# Conector.net
KiCad netlist of a schematic drawn in Altium Designer
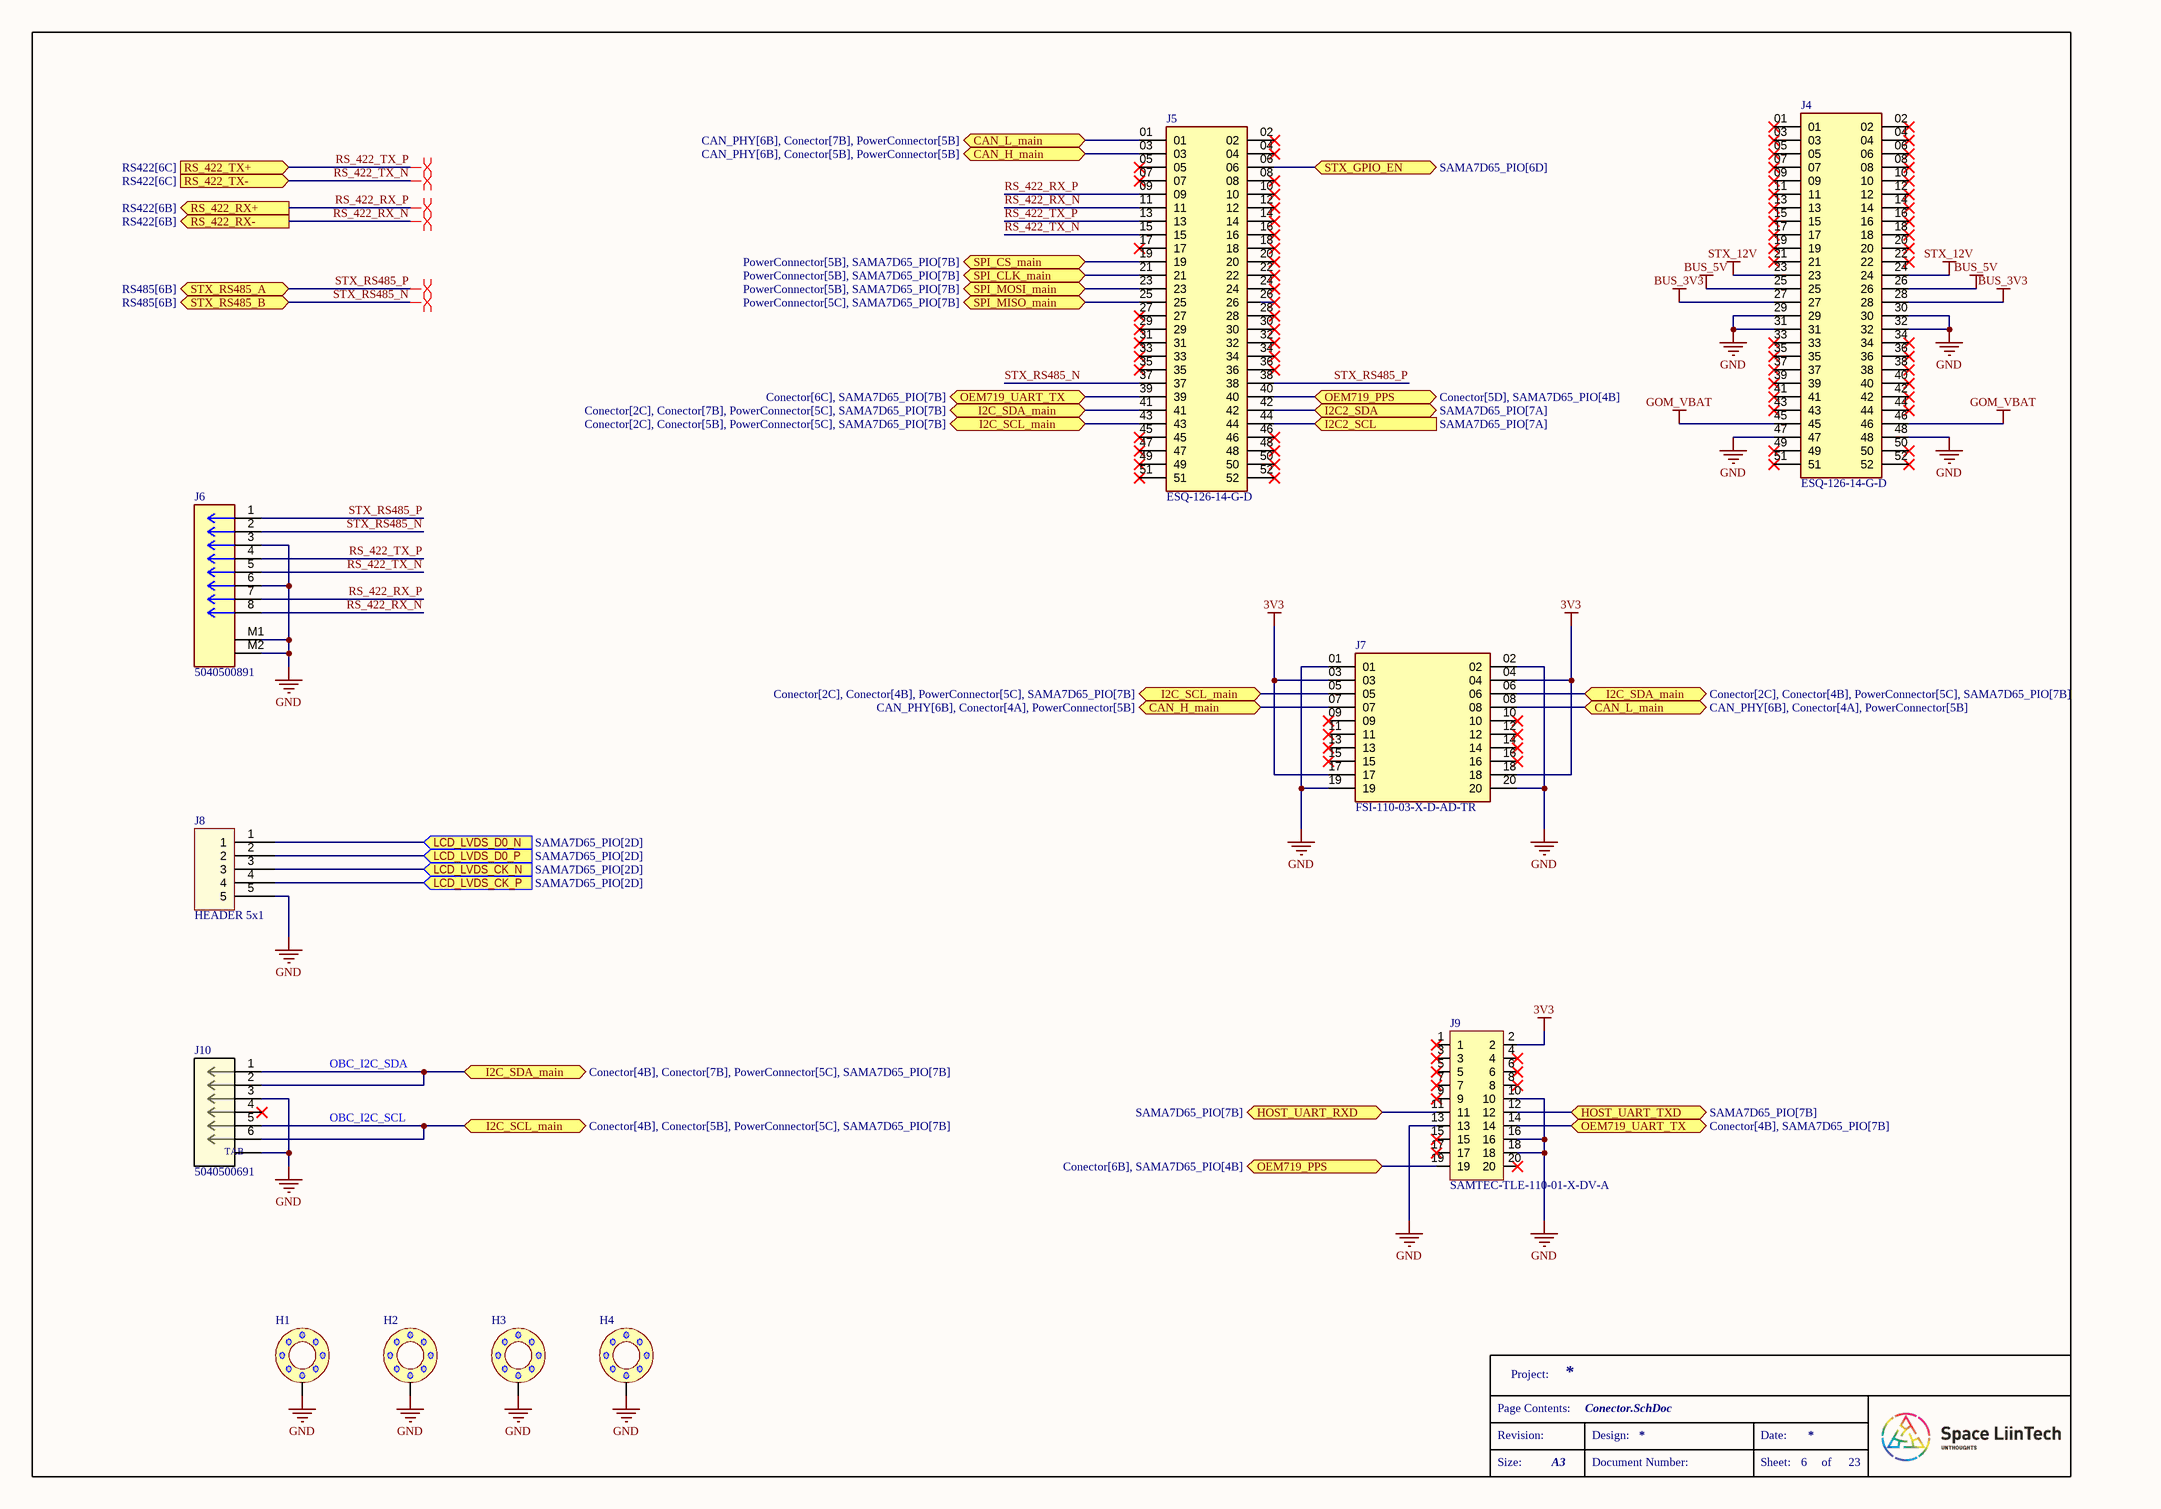
[diagram p0: Conector.SchDoc]

(export (version "E")
  (design (tool "Eeschema 10.0.6"))
  (components
    (comp (ref "H1")
      (value "hole_space")
      (footprint "HOLE_SPACE")
      (libsource (lib "IFBschelib") (part "hole_space"))
    )
    (comp (ref "H2")
      (value "hole_space")
      (footprint "HOLE_SPACE")
      (libsource (lib "IFBschelib") (part "hole_space"))
    )
    (comp (ref "H3")
      (value "hole_space")
      (footprint "HOLE_SPACE")
      (libsource (lib "IFBschelib") (part "hole_space"))
    )
    (comp (ref "H4")
      (value "hole_space")
      (footprint "HOLE_SPACE")
      (libsource (lib "IFBschelib") (part "hole_space"))
    )
    (comp (ref "J4")
      (value "ESQ-126-14-G-D")
      (footprint "ESQ-126-14-G-D")
      (fields (field (name "MF") "Samtec"))
      (libsource (lib "IFBschelib") (part "ESQ-126-14-G-D"))
    )
    (comp (ref "J5")
      (value "ESQ-126-14-G-D")
      (footprint "ESQ-126-14-G-D")
      (fields (field (name "MF") "Samtec"))
      (libsource (lib "IFBschelib") (part "ESQ-126-14-G-D"))
    )
    (comp (ref "J6")
      (value "5040500891")
      (footprint "MOLEX_5040500891")
      (description "Connector Header Surface Mount, Right Angle 8 position 0.059\" (1.50mm)`")
      (libsource (lib "IFBschelib") (part "5040500891"))
    )
    (comp (ref "J7")
      (value "FSI-110-03-X-D-AD-TR")
      (footprint "SAMTEC_FSI-110-03-X-D-AD-TR")
      (description "1mm SINGLE ELEMENT INTERFACE")
      (libsource (lib "IFBschelib") (part "FSI-110-03-X-D-AD-TR"))
    )
    (comp (ref "J8")
      (value "HEADER 5x1")
      (footprint "Header_254P_5x1")
      (libsource (lib "IFBschelib") (part "Header 5x1"))
    )
    (comp (ref "J9")
      (value "SAMTEC-TLE-110-01-X-DV-A")
      (footprint "SAMTEC-TLE-110-01-X-DV-A")
      (libsource (lib "IFBschelib") (part "SAMTEC-TLE-110-01-X-DV-A"))
    )
    (comp (ref "J10")
      (value "5040500691")
      (footprint "5040500691")
      (fields (field (name "COPYRIGHT") "Copyright (C) 2025 Ultra Librarian. All rights reserved."))
      (libsource (lib "IFBschelib") (part "5040500691"))
    )
  )
  (nets
    (net (code "1") (name "/CAN_H_main") (class "Default")
      (node (ref "J5") (pin "03") (pinfunction "03_03") (pintype "passive"))
      (node (ref "J7") (pin "07") (pinfunction "07_07") (pintype "passive"))
    )
    (net (code "2") (name "/CAN_L_main") (class "Default")
      (node (ref "J5") (pin "01") (pinfunction "01_01") (pintype "passive"))
      (node (ref "J7") (pin "08") (pinfunction "08_08") (pintype "passive"))
    )
    (net (code "3") (name "/HOST_UART_RXD") (class "Default")
      (node (ref "J9") (pin "11") (pinfunction "11_11") (pintype "passive"))
    )
    (net (code "4") (name "/HOST_UART_TXD") (class "Default")
      (node (ref "J9") (pin "12") (pinfunction "12_12") (pintype "passive"))
    )
    (net (code "5") (name "/I2C2_SCL") (class "Default")
      (node (ref "J5") (pin "44") (pinfunction "44_44") (pintype "passive"))
    )
    (net (code "6") (name "/I2C2_SDA") (class "Default")
      (node (ref "J5") (pin "42") (pinfunction "42_42") (pintype "passive"))
    )
    (net (code "7") (name "/I2C_SCL_main") (class "Default")
      (node (ref "J10") (pin "5") (pinfunction "5_5") (pintype "passive"))
      (node (ref "J10") (pin "6") (pinfunction "6_6") (pintype "passive"))
      (node (ref "J5") (pin "43") (pinfunction "43_43") (pintype "passive"))
      (node (ref "J7") (pin "05") (pinfunction "05_05") (pintype "passive"))
    )
    (net (code "8") (name "/I2C_SDA_main") (class "Default")
      (node (ref "J10") (pin "1") (pinfunction "1_1") (pintype "passive"))
      (node (ref "J10") (pin "2") (pinfunction "2_2") (pintype "passive"))
      (node (ref "J5") (pin "41") (pinfunction "41_41") (pintype "passive"))
      (node (ref "J7") (pin "06") (pinfunction "06_06") (pintype "passive"))
    )
    (net (code "9") (name "/LCD_LVDS_CK_N") (class "Default")
      (node (ref "J8") (pin "3") (pinfunction "3_3") (pintype "passive"))
    )
    (net (code "10") (name "/LCD_LVDS_CK_P") (class "Default")
      (node (ref "J8") (pin "4") (pinfunction "4_4") (pintype "passive"))
    )
    (net (code "11") (name "/LCD_LVDS_D0_N") (class "Default")
      (node (ref "J8") (pin "1") (pinfunction "1_1") (pintype "passive"))
    )
    (net (code "12") (name "/LCD_LVDS_D0_P") (class "Default")
      (node (ref "J8") (pin "2") (pinfunction "2_2") (pintype "passive"))
    )
    (net (code "13") (name "/OEM719_PPS") (class "Default")
      (node (ref "J5") (pin "40") (pinfunction "40_40") (pintype "passive"))
      (node (ref "J9") (pin "19") (pinfunction "19_19") (pintype "passive"))
    )
    (net (code "14") (name "/OEM719_UART_TX") (class "Default")
      (node (ref "J5") (pin "39") (pinfunction "39_39") (pintype "passive"))
      (node (ref "J9") (pin "14") (pinfunction "14_14") (pintype "passive"))
    )
    (net (code "15") (name "/RS_422_RX_N") (class "Default")
      (node (ref "J5") (pin "11") (pinfunction "11_11") (pintype "passive"))
      (node (ref "J6") (pin "8") (pinfunction "8_8") (pintype "passive"))
    )
    (net (code "16") (name "/RS_422_RX_P") (class "Default")
      (node (ref "J5") (pin "09") (pinfunction "09_09") (pintype "passive"))
      (node (ref "J6") (pin "7") (pinfunction "7_7") (pintype "passive"))
    )
    (net (code "17") (name "/RS_422_TX_N") (class "Default")
      (node (ref "J5") (pin "15") (pinfunction "15_15") (pintype "passive"))
      (node (ref "J6") (pin "5") (pinfunction "5_5") (pintype "passive"))
    )
    (net (code "18") (name "/RS_422_TX_P") (class "Default")
      (node (ref "J5") (pin "13") (pinfunction "13_13") (pintype "passive"))
      (node (ref "J6") (pin "4") (pinfunction "4_4") (pintype "passive"))
    )
    (net (code "19") (name "/SPI_CLK_main") (class "Default")
      (node (ref "J5") (pin "21") (pinfunction "21_21") (pintype "passive"))
    )
    (net (code "20") (name "/SPI_CS_main") (class "Default")
      (node (ref "J5") (pin "19") (pinfunction "19_19") (pintype "passive"))
    )
    (net (code "21") (name "/SPI_MISO_main") (class "Default")
      (node (ref "J5") (pin "25") (pinfunction "25_25") (pintype "passive"))
    )
    (net (code "22") (name "/SPI_MOSI_main") (class "Default")
      (node (ref "J5") (pin "23") (pinfunction "23_23") (pintype "passive"))
    )
    (net (code "23") (name "/STX_GPIO_EN") (class "Default")
      (node (ref "J5") (pin "06") (pinfunction "06_06") (pintype "passive"))
    )
    (net (code "24") (name "/STX_RS485_N") (class "Default")
      (node (ref "J5") (pin "37") (pinfunction "37_37") (pintype "passive"))
      (node (ref "J6") (pin "2") (pinfunction "2_2") (pintype "passive"))
    )
    (net (code "25") (name "/STX_RS485_P") (class "Default")
      (node (ref "J5") (pin "38") (pinfunction "38_38") (pintype "passive"))
      (node (ref "J6") (pin "1") (pinfunction "1_1") (pintype "passive"))
    )
    (net (code "26") (name "3V3") (class "Default")
      (node (ref "J7") (pin "03") (pinfunction "03_03") (pintype "passive"))
      (node (ref "J7") (pin "04") (pinfunction "04_04") (pintype "passive"))
      (node (ref "J7") (pin "17") (pinfunction "17_17") (pintype "passive"))
      (node (ref "J7") (pin "18") (pinfunction "18_18") (pintype "passive"))
      (node (ref "J9") (pin "2") (pinfunction "2_2") (pintype "passive"))
    )
    (net (code "27") (name "BUS_3V3") (class "Default")
      (node (ref "J4") (pin "27") (pinfunction "27_27") (pintype "passive"))
      (node (ref "J4") (pin "28") (pinfunction "28_28") (pintype "passive"))
    )
    (net (code "28") (name "BUS_5V") (class "Default")
      (node (ref "J4") (pin "25") (pinfunction "25_25") (pintype "passive"))
      (node (ref "J4") (pin "26") (pinfunction "26_26") (pintype "passive"))
    )
    (net (code "29") (name "GND") (class "Default")
      (node (ref "H1") (pin "1") (pinfunction "1_1") (pintype "passive"))
      (node (ref "H2") (pin "1") (pinfunction "1_1") (pintype "passive"))
      (node (ref "H3") (pin "1") (pinfunction "1_1") (pintype "passive"))
      (node (ref "H4") (pin "1") (pinfunction "1_1") (pintype "passive"))
      (node (ref "J10") (pin "3") (pinfunction "3_3") (pintype "passive"))
      (node (ref "J10") (pin "7") (pinfunction "7_7") (pintype "passive"))
      (node (ref "J4") (pin "29") (pinfunction "29_29") (pintype "passive"))
      (node (ref "J4") (pin "30") (pinfunction "30_30") (pintype "passive"))
      (node (ref "J4") (pin "31") (pinfunction "31_31") (pintype "passive"))
      (node (ref "J4") (pin "32") (pinfunction "32_32") (pintype "passive"))
      (node (ref "J4") (pin "47") (pinfunction "47_47") (pintype "passive"))
      (node (ref "J4") (pin "48") (pinfunction "48_48") (pintype "passive"))
      (node (ref "J6") (pin "3") (pinfunction "3_3") (pintype "passive"))
      (node (ref "J6") (pin "6") (pinfunction "6_6") (pintype "passive"))
      (node (ref "J6") (pin "M1") (pinfunction "M1_M1") (pintype "passive"))
      (node (ref "J6") (pin "M2") (pinfunction "M2_M2") (pintype "passive"))
      (node (ref "J7") (pin "01") (pinfunction "01_01") (pintype "passive"))
      (node (ref "J7") (pin "02") (pinfunction "02_02") (pintype "passive"))
      (node (ref "J7") (pin "19") (pinfunction "19_19") (pintype "passive"))
      (node (ref "J7") (pin "20") (pinfunction "20_20") (pintype "passive"))
      (node (ref "J8") (pin "5") (pinfunction "5_5") (pintype "passive"))
      (node (ref "J9") (pin "10") (pinfunction "10_10") (pintype "passive"))
      (node (ref "J9") (pin "13") (pinfunction "13_13") (pintype "passive"))
      (node (ref "J9") (pin "16") (pinfunction "16_16") (pintype "passive"))
      (node (ref "J9") (pin "18") (pinfunction "18_18") (pintype "passive"))
    )
    (net (code "30") (name "GOM_VBAT") (class "Default")
      (node (ref "J4") (pin "45") (pinfunction "45_45") (pintype "passive"))
      (node (ref "J4") (pin "46") (pinfunction "46_46") (pintype "passive"))
    )
    (net (code "31") (name "STX_12V") (class "Default")
      (node (ref "J4") (pin "23") (pinfunction "23_23") (pintype "passive"))
      (node (ref "J4") (pin "24") (pinfunction "24_24") (pintype "passive"))
    )
    (net (code "32") (name "unconnected-(J4-Pad01)") (class "Default")
      (node (ref "J4") (pin "01") (pinfunction "01_01") (pintype "passive+no_connect"))
    )
    (net (code "33") (name "unconnected-(J4-Pad02)") (class "Default")
      (node (ref "J4") (pin "02") (pinfunction "02_02") (pintype "passive+no_connect"))
    )
    (net (code "34") (name "unconnected-(J4-Pad03)") (class "Default")
      (node (ref "J4") (pin "03") (pinfunction "03_03") (pintype "passive+no_connect"))
    )
    (net (code "35") (name "unconnected-(J4-Pad04)") (class "Default")
      (node (ref "J4") (pin "04") (pinfunction "04_04") (pintype "passive+no_connect"))
    )
    (net (code "36") (name "unconnected-(J4-Pad05)") (class "Default")
      (node (ref "J4") (pin "05") (pinfunction "05_05") (pintype "passive+no_connect"))
    )
    (net (code "37") (name "unconnected-(J4-Pad06)") (class "Default")
      (node (ref "J4") (pin "06") (pinfunction "06_06") (pintype "passive+no_connect"))
    )
    (net (code "38") (name "unconnected-(J4-Pad07)") (class "Default")
      (node (ref "J4") (pin "07") (pinfunction "07_07") (pintype "passive+no_connect"))
    )
    (net (code "39") (name "unconnected-(J4-Pad08)") (class "Default")
      (node (ref "J4") (pin "08") (pinfunction "08_08") (pintype "passive+no_connect"))
    )
    (net (code "40") (name "unconnected-(J4-Pad09)") (class "Default")
      (node (ref "J4") (pin "09") (pinfunction "09_09") (pintype "passive+no_connect"))
    )
    (net (code "41") (name "unconnected-(J4-Pad10)") (class "Default")
      (node (ref "J4") (pin "10") (pinfunction "10_10") (pintype "passive+no_connect"))
    )
    (net (code "42") (name "unconnected-(J4-Pad11)") (class "Default")
      (node (ref "J4") (pin "11") (pinfunction "11_11") (pintype "passive+no_connect"))
    )
    (net (code "43") (name "unconnected-(J4-Pad12)") (class "Default")
      (node (ref "J4") (pin "12") (pinfunction "12_12") (pintype "passive+no_connect"))
    )
    (net (code "44") (name "unconnected-(J4-Pad13)") (class "Default")
      (node (ref "J4") (pin "13") (pinfunction "13_13") (pintype "passive+no_connect"))
    )
    (net (code "45") (name "unconnected-(J4-Pad14)") (class "Default")
      (node (ref "J4") (pin "14") (pinfunction "14_14") (pintype "passive+no_connect"))
    )
    (net (code "46") (name "unconnected-(J4-Pad15)") (class "Default")
      (node (ref "J4") (pin "15") (pinfunction "15_15") (pintype "passive+no_connect"))
    )
    (net (code "47") (name "unconnected-(J4-Pad16)") (class "Default")
      (node (ref "J4") (pin "16") (pinfunction "16_16") (pintype "passive+no_connect"))
    )
    (net (code "48") (name "unconnected-(J4-Pad17)") (class "Default")
      (node (ref "J4") (pin "17") (pinfunction "17_17") (pintype "passive+no_connect"))
    )
    (net (code "49") (name "unconnected-(J4-Pad18)") (class "Default")
      (node (ref "J4") (pin "18") (pinfunction "18_18") (pintype "passive+no_connect"))
    )
    (net (code "50") (name "unconnected-(J4-Pad19)") (class "Default")
      (node (ref "J4") (pin "19") (pinfunction "19_19") (pintype "passive+no_connect"))
    )
    (net (code "51") (name "unconnected-(J4-Pad20)") (class "Default")
      (node (ref "J4") (pin "20") (pinfunction "20_20") (pintype "passive+no_connect"))
    )
    (net (code "52") (name "unconnected-(J4-Pad21)") (class "Default")
      (node (ref "J4") (pin "21") (pinfunction "21_21") (pintype "passive+no_connect"))
    )
    (net (code "53") (name "unconnected-(J4-Pad22)") (class "Default")
      (node (ref "J4") (pin "22") (pinfunction "22_22") (pintype "passive+no_connect"))
    )
    (net (code "54") (name "unconnected-(J4-Pad33)") (class "Default")
      (node (ref "J4") (pin "33") (pinfunction "33_33") (pintype "passive+no_connect"))
    )
    (net (code "55") (name "unconnected-(J4-Pad34)") (class "Default")
      (node (ref "J4") (pin "34") (pinfunction "34_34") (pintype "passive+no_connect"))
    )
    (net (code "56") (name "unconnected-(J4-Pad35)") (class "Default")
      (node (ref "J4") (pin "35") (pinfunction "35_35") (pintype "passive+no_connect"))
    )
    (net (code "57") (name "unconnected-(J4-Pad36)") (class "Default")
      (node (ref "J4") (pin "36") (pinfunction "36_36") (pintype "passive+no_connect"))
    )
    (net (code "58") (name "unconnected-(J4-Pad37)") (class "Default")
      (node (ref "J4") (pin "37") (pinfunction "37_37") (pintype "passive+no_connect"))
    )
    (net (code "59") (name "unconnected-(J4-Pad38)") (class "Default")
      (node (ref "J4") (pin "38") (pinfunction "38_38") (pintype "passive+no_connect"))
    )
    (net (code "60") (name "unconnected-(J4-Pad39)") (class "Default")
      (node (ref "J4") (pin "39") (pinfunction "39_39") (pintype "passive+no_connect"))
    )
    (net (code "61") (name "unconnected-(J4-Pad40)") (class "Default")
      (node (ref "J4") (pin "40") (pinfunction "40_40") (pintype "passive+no_connect"))
    )
    (net (code "62") (name "unconnected-(J4-Pad41)") (class "Default")
      (node (ref "J4") (pin "41") (pinfunction "41_41") (pintype "passive+no_connect"))
    )
    (net (code "63") (name "unconnected-(J4-Pad42)") (class "Default")
      (node (ref "J4") (pin "42") (pinfunction "42_42") (pintype "passive+no_connect"))
    )
    (net (code "64") (name "unconnected-(J4-Pad43)") (class "Default")
      (node (ref "J4") (pin "43") (pinfunction "43_43") (pintype "passive+no_connect"))
    )
    (net (code "65") (name "unconnected-(J4-Pad44)") (class "Default")
      (node (ref "J4") (pin "44") (pinfunction "44_44") (pintype "passive+no_connect"))
    )
    (net (code "66") (name "unconnected-(J4-Pad49)") (class "Default")
      (node (ref "J4") (pin "49") (pinfunction "49_49") (pintype "passive+no_connect"))
    )
    (net (code "67") (name "unconnected-(J4-Pad50)") (class "Default")
      (node (ref "J4") (pin "50") (pinfunction "50_50") (pintype "passive+no_connect"))
    )
    (net (code "68") (name "unconnected-(J4-Pad51)") (class "Default")
      (node (ref "J4") (pin "51") (pinfunction "51_51") (pintype "passive+no_connect"))
    )
    (net (code "69") (name "unconnected-(J4-Pad52)") (class "Default")
      (node (ref "J4") (pin "52") (pinfunction "52_52") (pintype "passive+no_connect"))
    )
    (net (code "70") (name "unconnected-(J5-Pad02)") (class "Default")
      (node (ref "J5") (pin "02") (pinfunction "02_02") (pintype "passive+no_connect"))
    )
    (net (code "71") (name "unconnected-(J5-Pad04)") (class "Default")
      (node (ref "J5") (pin "04") (pinfunction "04_04") (pintype "passive+no_connect"))
    )
    (net (code "72") (name "unconnected-(J5-Pad05)") (class "Default")
      (node (ref "J5") (pin "05") (pinfunction "05_05") (pintype "passive+no_connect"))
    )
    (net (code "73") (name "unconnected-(J5-Pad07)") (class "Default")
      (node (ref "J5") (pin "07") (pinfunction "07_07") (pintype "passive+no_connect"))
    )
    (net (code "74") (name "unconnected-(J5-Pad08)") (class "Default")
      (node (ref "J5") (pin "08") (pinfunction "08_08") (pintype "passive+no_connect"))
    )
    (net (code "75") (name "unconnected-(J5-Pad10)") (class "Default")
      (node (ref "J5") (pin "10") (pinfunction "10_10") (pintype "passive+no_connect"))
    )
    (net (code "76") (name "unconnected-(J5-Pad12)") (class "Default")
      (node (ref "J5") (pin "12") (pinfunction "12_12") (pintype "passive+no_connect"))
    )
    (net (code "77") (name "unconnected-(J5-Pad14)") (class "Default")
      (node (ref "J5") (pin "14") (pinfunction "14_14") (pintype "passive+no_connect"))
    )
    (net (code "78") (name "unconnected-(J5-Pad16)") (class "Default")
      (node (ref "J5") (pin "16") (pinfunction "16_16") (pintype "passive+no_connect"))
    )
    (net (code "79") (name "unconnected-(J5-Pad17)") (class "Default")
      (node (ref "J5") (pin "17") (pinfunction "17_17") (pintype "passive+no_connect"))
    )
    (net (code "80") (name "unconnected-(J5-Pad18)") (class "Default")
      (node (ref "J5") (pin "18") (pinfunction "18_18") (pintype "passive+no_connect"))
    )
    (net (code "81") (name "unconnected-(J5-Pad20)") (class "Default")
      (node (ref "J5") (pin "20") (pinfunction "20_20") (pintype "passive+no_connect"))
    )
    (net (code "82") (name "unconnected-(J5-Pad22)") (class "Default")
      (node (ref "J5") (pin "22") (pinfunction "22_22") (pintype "passive+no_connect"))
    )
    (net (code "83") (name "unconnected-(J5-Pad24)") (class "Default")
      (node (ref "J5") (pin "24") (pinfunction "24_24") (pintype "passive+no_connect"))
    )
    (net (code "84") (name "unconnected-(J5-Pad26)") (class "Default")
      (node (ref "J5") (pin "26") (pinfunction "26_26") (pintype "passive+no_connect"))
    )
    (net (code "85") (name "unconnected-(J5-Pad27)") (class "Default")
      (node (ref "J5") (pin "27") (pinfunction "27_27") (pintype "passive+no_connect"))
    )
    (net (code "86") (name "unconnected-(J5-Pad28)") (class "Default")
      (node (ref "J5") (pin "28") (pinfunction "28_28") (pintype "passive+no_connect"))
    )
    (net (code "87") (name "unconnected-(J5-Pad29)") (class "Default")
      (node (ref "J5") (pin "29") (pinfunction "29_29") (pintype "passive+no_connect"))
    )
    (net (code "88") (name "unconnected-(J5-Pad30)") (class "Default")
      (node (ref "J5") (pin "30") (pinfunction "30_30") (pintype "passive+no_connect"))
    )
    (net (code "89") (name "unconnected-(J5-Pad31)") (class "Default")
      (node (ref "J5") (pin "31") (pinfunction "31_31") (pintype "passive+no_connect"))
    )
    (net (code "90") (name "unconnected-(J5-Pad32)") (class "Default")
      (node (ref "J5") (pin "32") (pinfunction "32_32") (pintype "passive+no_connect"))
    )
    (net (code "91") (name "unconnected-(J5-Pad33)") (class "Default")
      (node (ref "J5") (pin "33") (pinfunction "33_33") (pintype "passive+no_connect"))
    )
    (net (code "92") (name "unconnected-(J5-Pad34)") (class "Default")
      (node (ref "J5") (pin "34") (pinfunction "34_34") (pintype "passive+no_connect"))
    )
    (net (code "93") (name "unconnected-(J5-Pad35)") (class "Default")
      (node (ref "J5") (pin "35") (pinfunction "35_35") (pintype "passive+no_connect"))
    )
    (net (code "94") (name "unconnected-(J5-Pad36)") (class "Default")
      (node (ref "J5") (pin "36") (pinfunction "36_36") (pintype "passive+no_connect"))
    )
    (net (code "95") (name "unconnected-(J5-Pad45)") (class "Default")
      (node (ref "J5") (pin "45") (pinfunction "45_45") (pintype "passive+no_connect"))
    )
    (net (code "96") (name "unconnected-(J5-Pad46)") (class "Default")
      (node (ref "J5") (pin "46") (pinfunction "46_46") (pintype "passive+no_connect"))
    )
    (net (code "97") (name "unconnected-(J5-Pad47)") (class "Default")
      (node (ref "J5") (pin "47") (pinfunction "47_47") (pintype "passive+no_connect"))
    )
    (net (code "98") (name "unconnected-(J5-Pad48)") (class "Default")
      (node (ref "J5") (pin "48") (pinfunction "48_48") (pintype "passive+no_connect"))
    )
    (net (code "99") (name "unconnected-(J5-Pad49)") (class "Default")
      (node (ref "J5") (pin "49") (pinfunction "49_49") (pintype "passive+no_connect"))
    )
    (net (code "100") (name "unconnected-(J5-Pad50)") (class "Default")
      (node (ref "J5") (pin "50") (pinfunction "50_50") (pintype "passive+no_connect"))
    )
    (net (code "101") (name "unconnected-(J5-Pad51)") (class "Default")
      (node (ref "J5") (pin "51") (pinfunction "51_51") (pintype "passive+no_connect"))
    )
    (net (code "102") (name "unconnected-(J5-Pad52)") (class "Default")
      (node (ref "J5") (pin "52") (pinfunction "52_52") (pintype "passive+no_connect"))
    )
    (net (code "103") (name "unconnected-(J7-Pad09)") (class "Default")
      (node (ref "J7") (pin "09") (pinfunction "09_09") (pintype "passive+no_connect"))
    )
    (net (code "104") (name "unconnected-(J7-Pad10)") (class "Default")
      (node (ref "J7") (pin "10") (pinfunction "10_10") (pintype "passive+no_connect"))
    )
    (net (code "105") (name "unconnected-(J7-Pad11)") (class "Default")
      (node (ref "J7") (pin "11") (pinfunction "11_11") (pintype "passive+no_connect"))
    )
    (net (code "106") (name "unconnected-(J7-Pad12)") (class "Default")
      (node (ref "J7") (pin "12") (pinfunction "12_12") (pintype "passive+no_connect"))
    )
    (net (code "107") (name "unconnected-(J7-Pad13)") (class "Default")
      (node (ref "J7") (pin "13") (pinfunction "13_13") (pintype "passive+no_connect"))
    )
    (net (code "108") (name "unconnected-(J7-Pad14)") (class "Default")
      (node (ref "J7") (pin "14") (pinfunction "14_14") (pintype "passive+no_connect"))
    )
    (net (code "109") (name "unconnected-(J7-Pad15)") (class "Default")
      (node (ref "J7") (pin "15") (pinfunction "15_15") (pintype "passive+no_connect"))
    )
    (net (code "110") (name "unconnected-(J7-Pad16)") (class "Default")
      (node (ref "J7") (pin "16") (pinfunction "16_16") (pintype "passive+no_connect"))
    )
    (net (code "111") (name "unconnected-(J9-Pad1)") (class "Default")
      (node (ref "J9") (pin "1") (pinfunction "1_1") (pintype "passive+no_connect"))
    )
    (net (code "112") (name "unconnected-(J9-Pad3)") (class "Default")
      (node (ref "J9") (pin "3") (pinfunction "3_3") (pintype "passive+no_connect"))
    )
    (net (code "113") (name "unconnected-(J9-Pad4)") (class "Default")
      (node (ref "J9") (pin "4") (pinfunction "4_4") (pintype "passive+no_connect"))
    )
    (net (code "114") (name "unconnected-(J9-Pad5)") (class "Default")
      (node (ref "J9") (pin "5") (pinfunction "5_5") (pintype "passive+no_connect"))
    )
    (net (code "115") (name "unconnected-(J9-Pad6)") (class "Default")
      (node (ref "J9") (pin "6") (pinfunction "6_6") (pintype "passive+no_connect"))
    )
    (net (code "116") (name "unconnected-(J9-Pad7)") (class "Default")
      (node (ref "J9") (pin "7") (pinfunction "7_7") (pintype "passive+no_connect"))
    )
    (net (code "117") (name "unconnected-(J9-Pad8)") (class "Default")
      (node (ref "J9") (pin "8") (pinfunction "8_8") (pintype "passive+no_connect"))
    )
    (net (code "118") (name "unconnected-(J9-Pad9)") (class "Default")
      (node (ref "J9") (pin "9") (pinfunction "9_9") (pintype "passive+no_connect"))
    )
    (net (code "119") (name "unconnected-(J9-Pad15)") (class "Default")
      (node (ref "J9") (pin "15") (pinfunction "15_15") (pintype "passive+no_connect"))
    )
    (net (code "120") (name "unconnected-(J9-Pad17)") (class "Default")
      (node (ref "J9") (pin "17") (pinfunction "17_17") (pintype "passive+no_connect"))
    )
    (net (code "121") (name "unconnected-(J9-Pad20)") (class "Default")
      (node (ref "J9") (pin "20") (pinfunction "20_20") (pintype "passive+no_connect"))
    )
    (net (code "122") (name "unconnected-(J10-Pad4)") (class "Default")
      (node (ref "J10") (pin "4") (pinfunction "4_4") (pintype "passive+no_connect"))
    )
  )
)
